# RL_P.net
KiCad netlist of a schematic drawn in EAGLE
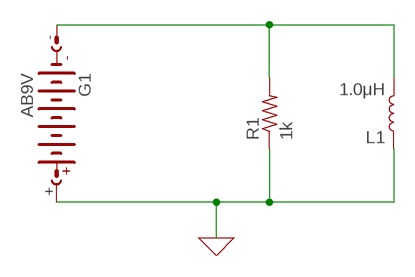
[diagram p0: schematic, sheet 1]

(export (version "E")
  (design (tool "Eeschema 10.0.6"))
  (components
    (comp (ref "G1")
      (value "AB9V")
      (footprint "eagle-import:AB9V")
      (libsource (lib "eagle-import") (part "AB9V"))
    )
    (comp (ref "L1")
      (value "1.0μH")
      (footprint "eagle-import:0805-WIDE")
      (libsource (lib "eagle-import") (part "1.0μH-0805_WIDE-1.0μH-1.4A-0.07OHM-1.4MM_H"))
    )
    (comp (ref "R1")
      (value "1k")
      (footprint "eagle-import:0204V")
      (libsource (lib "eagle-import") (part "R-US_0204/2V"))
    )
  )
  (nets
    (net (code "1") (name "GND") (class "Default")
      (node (ref "G1") (pin "+") (pinfunction "+_+") (pintype "passive"))
      (node (ref "L1") (pin "1") (pinfunction "1_1") (pintype "passive"))
      (node (ref "R1") (pin "1") (pinfunction "1_1") (pintype "passive"))
    )
    (net (code "2") (name "Net-(G1-Pad-)") (class "Default")
      (node (ref "G1") (pin "-") (pinfunction "-_-") (pintype "passive"))
      (node (ref "L1") (pin "2") (pinfunction "2_2") (pintype "passive"))
      (node (ref "R1") (pin "2") (pinfunction "2_2") (pintype "passive"))
    )
  )
)
